# USB-Hub.net
KiCad netlist of a schematic drawn in Altium Designer
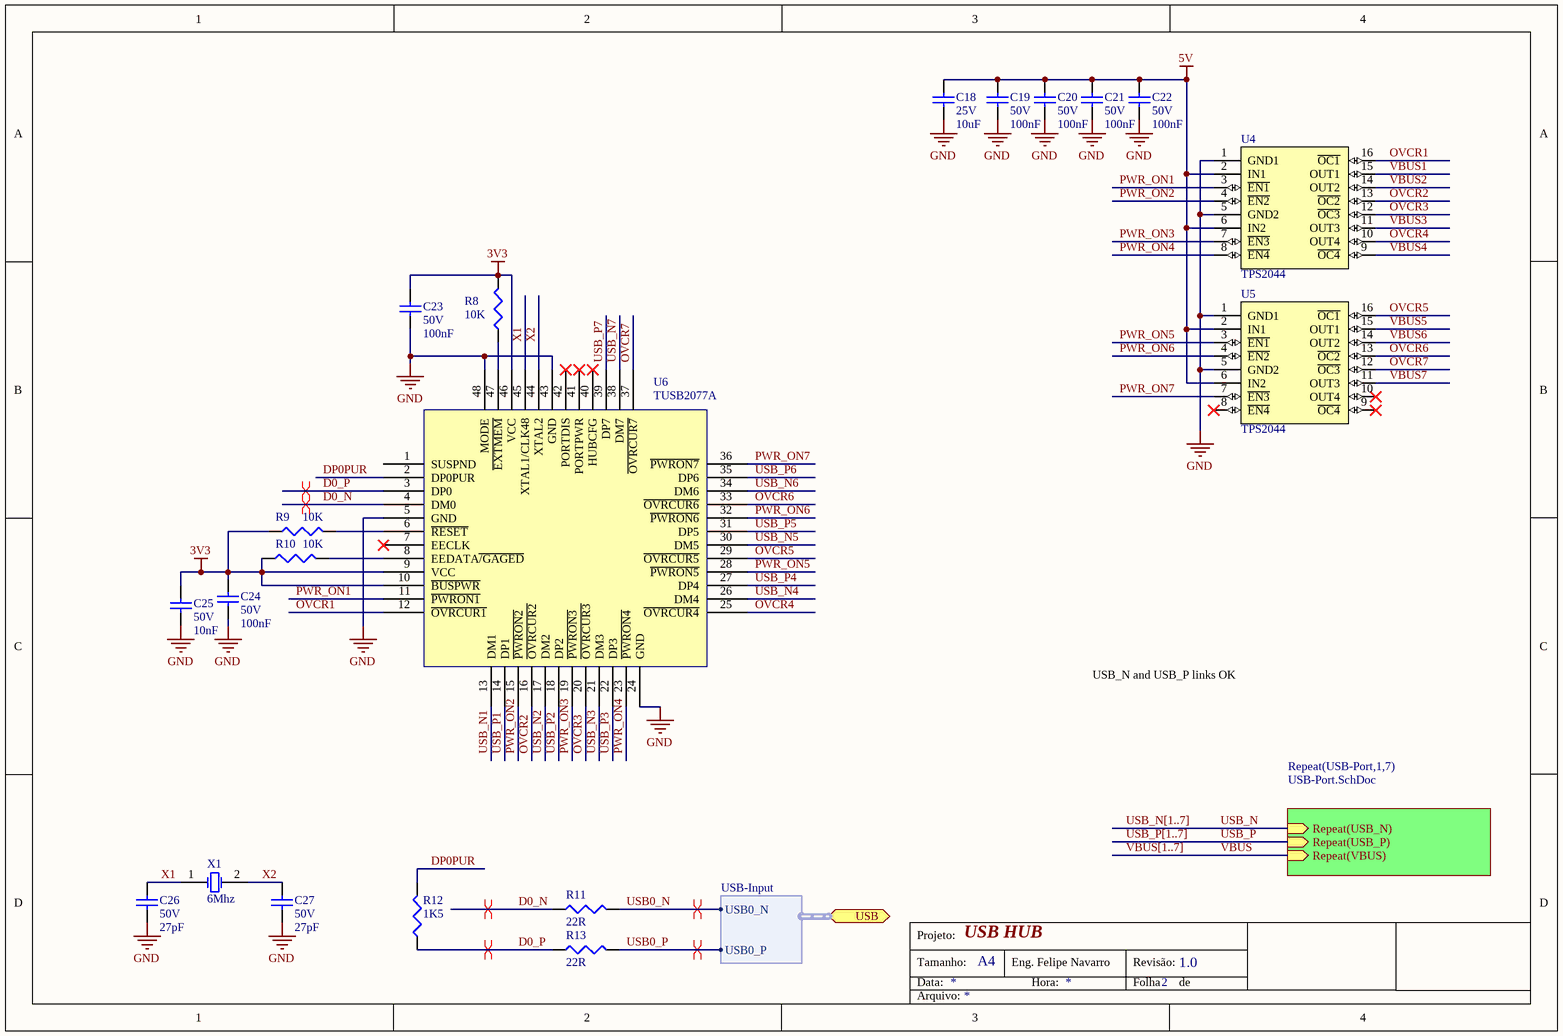
[diagram p0: USB-Hub.SchDoc]

(export (version "E")
  (design (tool "Eeschema 10.0.6"))
  (components
    (comp (ref "C18")
      (value "10uF")
      (footprint "CC0805")
      (description "Capacitor (Semiconductor SIM Model)")
      (fields (field (name "TENSÃO") "25V") (field (name "Comment") "Capacitor Cerâmico"))
      (libsource (lib "NavarroCAP") (part "Cap 10uF 25V 0805 X5R"))
    )
    (comp (ref "C19")
      (value "100nF")
      (footprint "CC0603")
      (description "Capacitor (Semiconductor SIM Model)")
      (fields (field (name "TENSÃO") "50V") (field (name "Comment") "Capacitor Cerâmico"))
      (libsource (lib "NavarroCAP") (part "Cap 100nF 50V 0603 X7R"))
    )
    (comp (ref "C20")
      (value "100nF")
      (footprint "CC0603")
      (description "Capacitor (Semiconductor SIM Model)")
      (fields (field (name "TENSÃO") "50V") (field (name "Comment") "Capacitor Cerâmico"))
      (libsource (lib "NavarroCAP") (part "Cap 100nF 50V 0603 X7R"))
    )
    (comp (ref "C21")
      (value "100nF")
      (footprint "CC0603")
      (description "Capacitor (Semiconductor SIM Model)")
      (fields (field (name "TENSÃO") "50V") (field (name "Comment") "Capacitor Cerâmico"))
      (libsource (lib "NavarroCAP") (part "Cap 100nF 50V 0603 X7R"))
    )
    (comp (ref "C22")
      (value "100nF")
      (footprint "CC0603")
      (description "Capacitor (Semiconductor SIM Model)")
      (fields (field (name "TENSÃO") "50V") (field (name "Comment") "Capacitor Cerâmico"))
      (libsource (lib "NavarroCAP") (part "Cap 100nF 50V 0603 X7R"))
    )
    (comp (ref "C23")
      (value "100nF")
      (footprint "CC0603")
      (description "Capacitor (Semiconductor SIM Model)")
      (fields (field (name "TENSÃO") "50V") (field (name "Comment") "Capacitor Cerâmico"))
      (libsource (lib "NavarroCAP") (part "Cap 100nF 50V 0603 X7R"))
    )
    (comp (ref "C24")
      (value "100nF")
      (footprint "CC0603")
      (description "Capacitor (Semiconductor SIM Model)")
      (fields (field (name "TENSÃO") "50V") (field (name "Comment") "Capacitor Cerâmico"))
      (libsource (lib "NavarroCAP") (part "Cap 100nF 50V 0603 X7R"))
    )
    (comp (ref "C25")
      (value "10nF")
      (footprint "CC0603")
      (description "Capacitor (Semiconductor SIM Model)")
      (fields (field (name "TENSÃO") "50V") (field (name "Comment") "Capacitor Cerâmico"))
      (libsource (lib "NavarroCAP") (part "Cap 10nF 50V 0603 X7R 5%"))
    )
    (comp (ref "C26")
      (value "27pF")
      (footprint "CC0603")
      (description "Capacitor (Semiconductor SIM Model)")
      (fields (field (name "TENSÃO") "50V") (field (name "Comment") "Capacitor Cerâmico"))
      (libsource (lib "NavarroCAP") (part "Cap 27pF 50V 0603 NP0"))
    )
    (comp (ref "C27")
      (value "27pF")
      (footprint "CC0603")
      (description "Capacitor (Semiconductor SIM Model)")
      (fields (field (name "TENSÃO") "50V") (field (name "Comment") "Capacitor Cerâmico"))
      (libsource (lib "NavarroCAP") (part "Cap 27pF 50V 0603 NP0"))
    )
    (comp (ref "R8")
      (value "10K")
      (footprint "CC0603")
      (description "Resistor")
      (libsource (lib "NavarroRES") (part "Res 10K 1% 0603 1/10W"))
    )
    (comp (ref "R9")
      (value "10K")
      (footprint "CC0603")
      (description "Resistor")
      (libsource (lib "NavarroRES") (part "Res 10K 1% 0603 1/10W"))
    )
    (comp (ref "R10")
      (value "10K")
      (footprint "CC0603")
      (description "Resistor")
      (libsource (lib "NavarroRES") (part "Res 10K 1% 0603 1/10W"))
    )
    (comp (ref "R11")
      (value "22R")
      (footprint "CC0603")
      (description "Resistor")
      (libsource (lib "NavarroRES") (part "Res 22R 1% 0603 1/10W"))
    )
    (comp (ref "R12")
      (value "1K5")
      (footprint "CC0603")
      (description "Resistor")
      (libsource (lib "NavarroRES") (part "Res 1K5 1% 0603 1/10W"))
    )
    (comp (ref "R13")
      (value "22R")
      (footprint "CC0603")
      (description "Resistor")
      (libsource (lib "NavarroRES") (part "Res 22R 1% 0603 1/10W"))
    )
    (comp (ref "U4")
      (value "TPS2044")
      (footprint "SOIC-16N")
      (description "QUAD POWER-DISTRIBUTION SWITCH")
      (libsource (lib "Navarro") (part "TPS2044"))
    )
    (comp (ref "U5")
      (value "TPS2044")
      (footprint "SOIC-16N")
      (description "QUAD POWER-DISTRIBUTION SWITCH")
      (libsource (lib "Navarro") (part "TPS2044"))
    )
    (comp (ref "U6")
      (value "TUSB2077A")
      (footprint "TQFP-48N")
      (description "USB HUB 7 Port")
      (libsource (lib "Navarro") (part "TUSB2077A"))
    )
    (comp (ref "X1")
      (value "6Mhz")
      (footprint "HC/49US")
      (description "Crystal Oscillator")
      (libsource (lib "Navarro") (part "XTAL"))
    )
  )
  (nets
    (net (code "2") (name "/D0_N") (class "Default")
      (node (ref "R11") (pin "1") (pinfunction "1_1") (pintype "passive"))
      (node (ref "U6") (pin "4") (pinfunction "DM0_4") (pintype "passive"))
    )
    (net (code "3") (name "/D0_P") (class "Default")
      (node (ref "R12") (pin "1") (pinfunction "1_1") (pintype "passive"))
      (node (ref "R13") (pin "1") (pinfunction "1_1") (pintype "passive"))
      (node (ref "U6") (pin "3") (pinfunction "DP0_3") (pintype "passive"))
    )
    (net (code "4") (name "/DP0PUR") (class "Default")
      (node (ref "R12") (pin "2") (pinfunction "2_2") (pintype "passive"))
      (node (ref "U6") (pin "2") (pinfunction "DP0PUR_2") (pintype "passive"))
    )
    (net (code "5") (name "/OVCR1") (class "Default")
      (node (ref "U4") (pin "16") (pinfunction "~{OC1}_16") (pintype "bidirectional"))
      (node (ref "U6") (pin "12") (pinfunction "~{OVRCUR1}_12") (pintype "passive"))
    )
    (net (code "6") (name "/OVCR2") (class "Default")
      (node (ref "U4") (pin "13") (pinfunction "~{OC2}_13") (pintype "bidirectional"))
      (node (ref "U6") (pin "16") (pinfunction "~{OVRCUR2}_16") (pintype "passive"))
    )
    (net (code "7") (name "/OVCR3") (class "Default")
      (node (ref "U4") (pin "12") (pinfunction "~{OC3}_12") (pintype "bidirectional"))
      (node (ref "U6") (pin "20") (pinfunction "~{OVRCUR3}_20") (pintype "passive"))
    )
    (net (code "8") (name "/OVCR4") (class "Default")
      (node (ref "U4") (pin "10") (pinfunction "OUT4_10") (pintype "bidirectional"))
      (node (ref "U6") (pin "25") (pinfunction "~{OVRCUR4}_25") (pintype "passive"))
    )
    (net (code "9") (name "/OVCR5") (class "Default")
      (node (ref "U5") (pin "16") (pinfunction "~{OC1}_16") (pintype "bidirectional"))
      (node (ref "U6") (pin "29") (pinfunction "~{OVRCUR5}_29") (pintype "passive"))
    )
    (net (code "10") (name "/OVCR6") (class "Default")
      (node (ref "U5") (pin "13") (pinfunction "~{OC2}_13") (pintype "bidirectional"))
      (node (ref "U6") (pin "33") (pinfunction "~{OVRCUR6}_33") (pintype "passive"))
    )
    (net (code "11") (name "/OVCR7") (class "Default")
      (node (ref "U5") (pin "12") (pinfunction "~{OC3}_12") (pintype "bidirectional"))
      (node (ref "U6") (pin "37") (pinfunction "~{OVRCUR7}_37") (pintype "passive"))
    )
    (net (code "12") (name "/PWR_ON1") (class "Default")
      (node (ref "U4") (pin "3") (pinfunction "~{EN1}_3") (pintype "bidirectional"))
      (node (ref "U6") (pin "11") (pinfunction "~{PWRON1}_11") (pintype "passive"))
    )
    (net (code "13") (name "/PWR_ON2") (class "Default")
      (node (ref "U4") (pin "4") (pinfunction "~{EN2}_4") (pintype "bidirectional"))
      (node (ref "U6") (pin "15") (pinfunction "~{PWRON2}_15") (pintype "passive"))
    )
    (net (code "14") (name "/PWR_ON3") (class "Default")
      (node (ref "U4") (pin "7") (pinfunction "~{EN3}_7") (pintype "bidirectional"))
      (node (ref "U6") (pin "19") (pinfunction "~{PWRON3}_19") (pintype "passive"))
    )
    (net (code "15") (name "/PWR_ON4") (class "Default")
      (node (ref "U4") (pin "8") (pinfunction "~{EN4}_8") (pintype "bidirectional"))
      (node (ref "U6") (pin "23") (pinfunction "~{PWRON4}_23") (pintype "passive"))
    )
    (net (code "16") (name "/PWR_ON5") (class "Default")
      (node (ref "U5") (pin "3") (pinfunction "~{EN1}_3") (pintype "bidirectional"))
      (node (ref "U6") (pin "28") (pinfunction "~{PWRON5}_28") (pintype "passive"))
    )
    (net (code "17") (name "/PWR_ON6") (class "Default")
      (node (ref "U5") (pin "4") (pinfunction "~{EN2}_4") (pintype "bidirectional"))
      (node (ref "U6") (pin "32") (pinfunction "~{PWRON6}_32") (pintype "passive"))
    )
    (net (code "18") (name "/PWR_ON7") (class "Default")
      (node (ref "U5") (pin "7") (pinfunction "~{EN3}_7") (pintype "bidirectional"))
      (node (ref "U6") (pin "36") (pinfunction "~{PWRON7}_36") (pintype "passive"))
    )
    (net (code "19") (name "/USB0_N") (class "Default")
      (node (ref "R11") (pin "2") (pinfunction "2_2") (pintype "passive"))
    )
    (net (code "20") (name "/USB0_P") (class "Default")
      (node (ref "R13") (pin "2") (pinfunction "2_2") (pintype "passive"))
    )
    (net (code "22") (name "/USB_N1") (class "Default")
      (node (ref "U6") (pin "13") (pinfunction "DM1_13") (pintype "passive"))
    )
    (net (code "23") (name "/USB_N2") (class "Default")
      (node (ref "U6") (pin "17") (pinfunction "DM2_17") (pintype "passive"))
    )
    (net (code "24") (name "/USB_N3") (class "Default")
      (node (ref "U6") (pin "21") (pinfunction "DM3_21") (pintype "passive"))
    )
    (net (code "25") (name "/USB_N4") (class "Default")
      (node (ref "U6") (pin "26") (pinfunction "DM4_26") (pintype "passive"))
    )
    (net (code "26") (name "/USB_N5") (class "Default")
      (node (ref "U6") (pin "30") (pinfunction "DM5_30") (pintype "passive"))
    )
    (net (code "27") (name "/USB_N6") (class "Default")
      (node (ref "U6") (pin "34") (pinfunction "DM6_34") (pintype "passive"))
    )
    (net (code "28") (name "/USB_N7") (class "Default")
      (node (ref "U6") (pin "38") (pinfunction "DM7_38") (pintype "passive"))
    )
    (net (code "31") (name "/USB_P1") (class "Default")
      (node (ref "U6") (pin "14") (pinfunction "DP1_14") (pintype "passive"))
    )
    (net (code "32") (name "/USB_P2") (class "Default")
      (node (ref "U6") (pin "18") (pinfunction "DP2_18") (pintype "passive"))
    )
    (net (code "33") (name "/USB_P3") (class "Default")
      (node (ref "U6") (pin "22") (pinfunction "DP3_22") (pintype "passive"))
    )
    (net (code "34") (name "/USB_P4") (class "Default")
      (node (ref "U6") (pin "27") (pinfunction "DP4_27") (pintype "passive"))
    )
    (net (code "35") (name "/USB_P5") (class "Default")
      (node (ref "U6") (pin "31") (pinfunction "DP5_31") (pintype "passive"))
    )
    (net (code "36") (name "/USB_P6") (class "Default")
      (node (ref "U6") (pin "35") (pinfunction "DP6_35") (pintype "passive"))
    )
    (net (code "37") (name "/USB_P7") (class "Default")
      (node (ref "U6") (pin "39") (pinfunction "DP7_39") (pintype "passive"))
    )
    (net (code "40") (name "/VBUS1") (class "Default")
      (node (ref "U4") (pin "15") (pinfunction "OUT1_15") (pintype "bidirectional"))
    )
    (net (code "41") (name "/VBUS2") (class "Default")
      (node (ref "U4") (pin "14") (pinfunction "OUT2_14") (pintype "bidirectional"))
    )
    (net (code "42") (name "/VBUS3") (class "Default")
      (node (ref "U4") (pin "11") (pinfunction "OUT3_11") (pintype "bidirectional"))
    )
    (net (code "43") (name "/VBUS4") (class "Default")
      (node (ref "U4") (pin "9") (pinfunction "~{OC4}_9") (pintype "bidirectional"))
    )
    (net (code "44") (name "/VBUS5") (class "Default")
      (node (ref "U5") (pin "15") (pinfunction "OUT1_15") (pintype "bidirectional"))
    )
    (net (code "45") (name "/VBUS6") (class "Default")
      (node (ref "U5") (pin "14") (pinfunction "OUT2_14") (pintype "bidirectional"))
    )
    (net (code "46") (name "/VBUS7") (class "Default")
      (node (ref "U5") (pin "11") (pinfunction "OUT3_11") (pintype "bidirectional"))
    )
    (net (code "48") (name "/X1") (class "Default")
      (node (ref "C26") (pin "2") (pinfunction "2_2") (pintype "passive"))
      (node (ref "U6") (pin "45") (pinfunction "XTAL1/CLK48_45") (pintype "passive"))
      (node (ref "X1") (pin "1") (pinfunction "OSC1_1") (pintype "passive"))
    )
    (net (code "49") (name "/X2") (class "Default")
      (node (ref "C27") (pin "2") (pinfunction "2_2") (pintype "passive"))
      (node (ref "U6") (pin "44") (pinfunction "XTAL2_44") (pintype "passive"))
      (node (ref "X1") (pin "2") (pinfunction "OSC2_2") (pintype "passive"))
    )
    (net (code "51") (name "3V3") (class "Default")
      (node (ref "C23") (pin "2") (pinfunction "2_2") (pintype "passive"))
      (node (ref "C24") (pin "2") (pinfunction "2_2") (pintype "passive"))
      (node (ref "C25") (pin "2") (pinfunction "2_2") (pintype "passive"))
      (node (ref "R10") (pin "1") (pinfunction "1_1") (pintype "passive"))
      (node (ref "R8") (pin "2") (pinfunction "2_2") (pintype "passive"))
      (node (ref "R9") (pin "1") (pinfunction "1_1") (pintype "passive"))
      (node (ref "U6") (pin "10") (pinfunction "~{BUSPWR}_10") (pintype "passive"))
      (node (ref "U6") (pin "46") (pinfunction "VCC_46") (pintype "power_in"))
      (node (ref "U6") (pin "9") (pinfunction "VCC_9") (pintype "power_in"))
    )
    (net (code "52") (name "5V") (class "Default")
      (node (ref "C18") (pin "2") (pinfunction "2_2") (pintype "passive"))
      (node (ref "C19") (pin "2") (pinfunction "2_2") (pintype "passive"))
      (node (ref "C20") (pin "2") (pinfunction "2_2") (pintype "passive"))
      (node (ref "C21") (pin "2") (pinfunction "2_2") (pintype "passive"))
      (node (ref "C22") (pin "2") (pinfunction "2_2") (pintype "passive"))
      (node (ref "U4") (pin "2") (pinfunction "IN1_2") (pintype "power_in"))
      (node (ref "U4") (pin "6") (pinfunction "IN2_6") (pintype "power_in"))
      (node (ref "U5") (pin "2") (pinfunction "IN1_2") (pintype "power_in"))
      (node (ref "U5") (pin "6") (pinfunction "IN2_6") (pintype "power_in"))
    )
    (net (code "53") (name "GND") (class "Default")
      (node (ref "C18") (pin "1") (pinfunction "1_1") (pintype "passive"))
      (node (ref "C19") (pin "1") (pinfunction "1_1") (pintype "passive"))
      (node (ref "C20") (pin "1") (pinfunction "1_1") (pintype "passive"))
      (node (ref "C21") (pin "1") (pinfunction "1_1") (pintype "passive"))
      (node (ref "C22") (pin "1") (pinfunction "1_1") (pintype "passive"))
      (node (ref "C23") (pin "1") (pinfunction "1_1") (pintype "passive"))
      (node (ref "C24") (pin "1") (pinfunction "1_1") (pintype "passive"))
      (node (ref "C25") (pin "1") (pinfunction "1_1") (pintype "passive"))
      (node (ref "C26") (pin "1") (pinfunction "1_1") (pintype "passive"))
      (node (ref "C27") (pin "1") (pinfunction "1_1") (pintype "passive"))
      (node (ref "U4") (pin "1") (pinfunction "GND1_1") (pintype "power_in"))
      (node (ref "U4") (pin "5") (pinfunction "GND2_5") (pintype "power_in"))
      (node (ref "U5") (pin "1") (pinfunction "GND1_1") (pintype "power_in"))
      (node (ref "U5") (pin "5") (pinfunction "GND2_5") (pintype "power_in"))
      (node (ref "U6") (pin "24") (pinfunction "GND_24") (pintype "power_in"))
      (node (ref "U6") (pin "43") (pinfunction "GND_43") (pintype "power_in"))
      (node (ref "U6") (pin "48") (pinfunction "MODE_48") (pintype "passive"))
      (node (ref "U6") (pin "5") (pinfunction "GND_5") (pintype "power_in"))
    )
    (net (code "54") (name "Net-(U6-EEDATA~{{slash}GAGED})") (class "Default")
      (node (ref "R10") (pin "2") (pinfunction "2_2") (pintype "passive"))
      (node (ref "U6") (pin "8") (pinfunction "EEDATA~{/GAGED}_8") (pintype "passive"))
    )
    (net (code "55") (name "Net-(U6-~{EXTMEM})") (class "Default")
      (node (ref "R8") (pin "1") (pinfunction "1_1") (pintype "passive"))
      (node (ref "U6") (pin "47") (pinfunction "~{EXTMEM}_47") (pintype "passive"))
    )
    (net (code "56") (name "Net-(U6-~{RESET})") (class "Default")
      (node (ref "R9") (pin "2") (pinfunction "2_2") (pintype "passive"))
      (node (ref "U6") (pin "6") (pinfunction "~{RESET}_6") (pintype "passive"))
    )
    (net (code "57") (name "unconnected-(U5-OUT4-Pad10)") (class "Default")
      (node (ref "U5") (pin "10") (pinfunction "OUT4_10") (pintype "bidirectional+no_connect"))
    )
    (net (code "58") (name "unconnected-(U5-~{EN4}-Pad8)") (class "Default")
      (node (ref "U5") (pin "8") (pinfunction "~{EN4}_8") (pintype "bidirectional+no_connect"))
    )
    (net (code "59") (name "unconnected-(U5-~{OC4}-Pad9)") (class "Default")
      (node (ref "U5") (pin "9") (pinfunction "~{OC4}_9") (pintype "bidirectional+no_connect"))
    )
    (net (code "60") (name "unconnected-(U6-EECLK-Pad7)") (class "Default")
      (node (ref "U6") (pin "7") (pinfunction "EECLK_7") (pintype "passive+no_connect"))
    )
    (net (code "61") (name "unconnected-(U6-HUBCFG-Pad40)") (class "Default")
      (node (ref "U6") (pin "40") (pinfunction "HUBCFG_40") (pintype "passive+no_connect"))
    )
    (net (code "62") (name "unconnected-(U6-PORTDIS-Pad42)") (class "Default")
      (node (ref "U6") (pin "42") (pinfunction "PORTDIS_42") (pintype "passive+no_connect"))
    )
    (net (code "63") (name "unconnected-(U6-PORTPWR-Pad41)") (class "Default")
      (node (ref "U6") (pin "41") (pinfunction "PORTPWR_41") (pintype "passive+no_connect"))
    )
    (net (code "64") (name "unconnected-(U6-SUSPND-Pad1)") (class "Default")
      (node (ref "U6") (pin "1") (pinfunction "SUSPND_1") (pintype "passive"))
    )
  )
)
